# rocketBoard.net
KiCad netlist of a schematic drawn in EAGLE
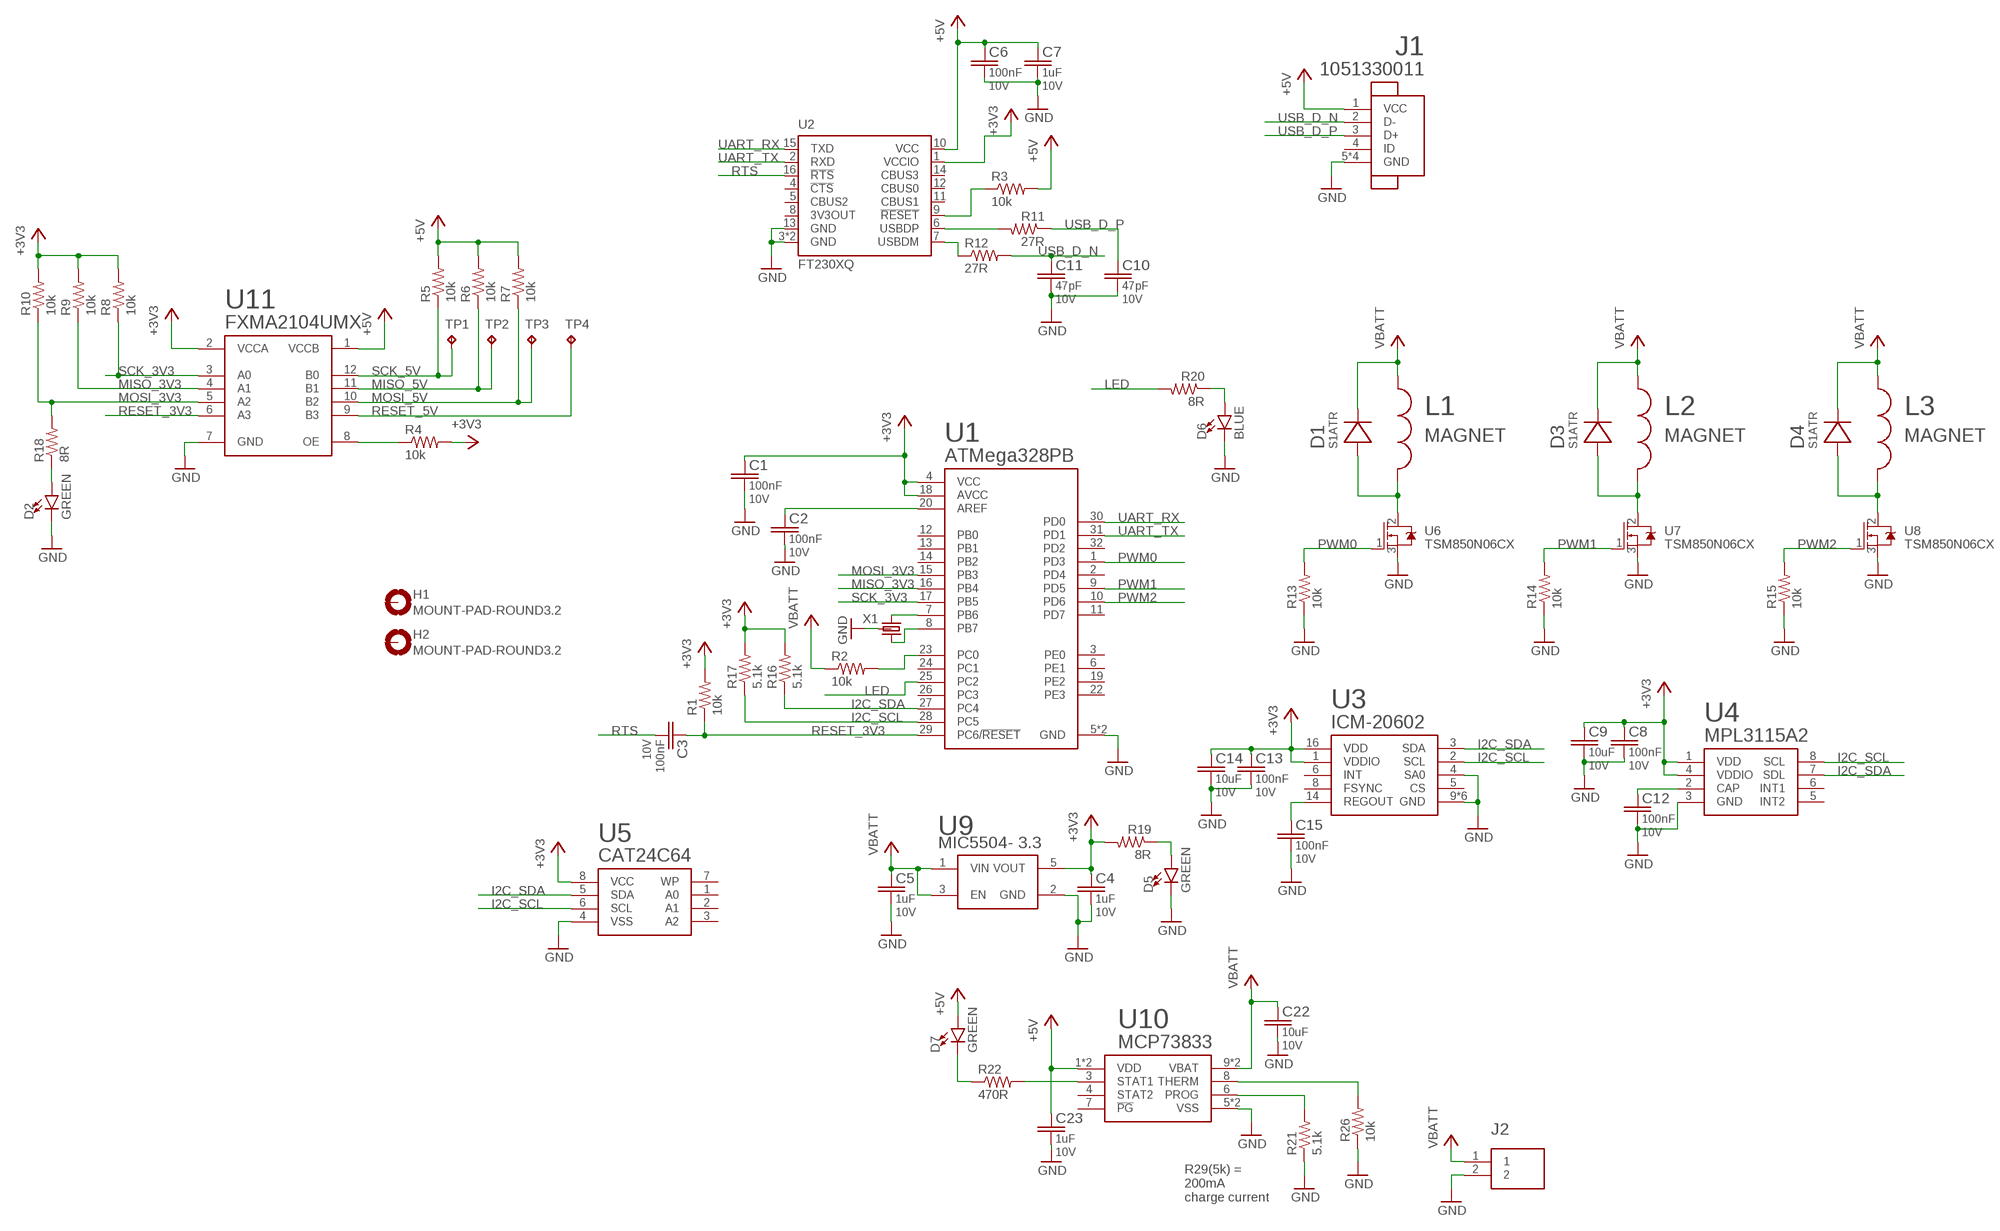
[diagram p0: schematic, sheet 1]

(export (version "E")
  (design (tool "Eeschema 10.0.6"))
  (components
    (comp (ref "C1")
      (value "100nF")
      (footprint "eagle-import:C0402")
      (fields (field (name "RATING") "10V"))
      (libsource (lib "eagle-import") (part "CL05A104MP5NNNC"))
    )
    (comp (ref "C2")
      (value "100nF")
      (footprint "eagle-import:C0402")
      (fields (field (name "RATING") "10V"))
      (libsource (lib "eagle-import") (part "CL05A104MP5NNNC"))
    )
    (comp (ref "C3")
      (value "100nF")
      (footprint "eagle-import:C0402")
      (fields (field (name "RATING") "10V"))
      (libsource (lib "eagle-import") (part "CL05A104MP5NNNC"))
    )
    (comp (ref "C4")
      (value "1uF")
      (footprint "eagle-import:C0402")
      (fields (field (name "RATING") "10V"))
      (libsource (lib "eagle-import") (part "CL05A105MP5NNNC"))
    )
    (comp (ref "C5")
      (value "1uF")
      (footprint "eagle-import:C0402")
      (fields (field (name "RATING") "10V"))
      (libsource (lib "eagle-import") (part "CL05A105MP5NNNC"))
    )
    (comp (ref "C6")
      (value "100nF")
      (footprint "eagle-import:C0402")
      (fields (field (name "RATING") "10V"))
      (libsource (lib "eagle-import") (part "CL05A104MP5NNNC"))
    )
    (comp (ref "C7")
      (value "1uF")
      (footprint "eagle-import:C0402")
      (fields (field (name "RATING") "10V"))
      (libsource (lib "eagle-import") (part "CL05A105MP5NNNC"))
    )
    (comp (ref "C8")
      (value "100nF")
      (footprint "eagle-import:C0402")
      (fields (field (name "RATING") "10V"))
      (libsource (lib "eagle-import") (part "CL05A104MP5NNNC"))
    )
    (comp (ref "C9")
      (value "10uF")
      (footprint "eagle-import:C0603")
      (fields (field (name "RATING") "10V"))
      (libsource (lib "eagle-import") (part "GRM188R61A106KE69D"))
    )
    (comp (ref "C10")
      (value "47pF")
      (footprint "eagle-import:C0402")
      (fields (field (name "RATING") "10V"))
      (libsource (lib "eagle-import") (part "885012005011"))
    )
    (comp (ref "C11")
      (value "47pF")
      (footprint "eagle-import:C0402")
      (fields (field (name "RATING") "10V"))
      (libsource (lib "eagle-import") (part "885012005011"))
    )
    (comp (ref "C12")
      (value "100nF")
      (footprint "eagle-import:C0402")
      (fields (field (name "RATING") "10V"))
      (libsource (lib "eagle-import") (part "CL05A104MP5NNNC"))
    )
    (comp (ref "C13")
      (value "100nF")
      (footprint "eagle-import:C0402")
      (fields (field (name "RATING") "10V"))
      (libsource (lib "eagle-import") (part "CL05A104MP5NNNC"))
    )
    (comp (ref "C14")
      (value "10uF")
      (footprint "eagle-import:C0603")
      (fields (field (name "RATING") "10V"))
      (libsource (lib "eagle-import") (part "GRM188R61A106KE69D"))
    )
    (comp (ref "C15")
      (value "100nF")
      (footprint "eagle-import:C0402")
      (fields (field (name "RATING") "10V"))
      (libsource (lib "eagle-import") (part "CL05A104MP5NNNC"))
    )
    (comp (ref "C22")
      (value "10uF")
      (footprint "eagle-import:C0603")
      (fields (field (name "RATING") "10V"))
      (libsource (lib "eagle-import") (part "GRM188R61A106KE69D"))
    )
    (comp (ref "C23")
      (value "1uF")
      (footprint "eagle-import:C0402")
      (fields (field (name "RATING") "10V"))
      (libsource (lib "eagle-import") (part "CL05A105MP5NNNC"))
    )
    (comp (ref "D1")
      (value "S1ATRSMA")
      (footprint "eagle-import:SODFL5226X295")
      (libsource (lib "eagle-import") (part "S1ATRSMA"))
    )
    (comp (ref "D2")
      (value "GREEN")
      (footprint "eagle-import:LED-0603")
      (libsource (lib "eagle-import") (part "LED-GREEN0603"))
    )
    (comp (ref "D3")
      (value "S1ATRSMA")
      (footprint "eagle-import:SODFL5226X295")
      (libsource (lib "eagle-import") (part "S1ATRSMA"))
    )
    (comp (ref "D4")
      (value "S1ATRSMA")
      (footprint "eagle-import:SODFL5226X295")
      (libsource (lib "eagle-import") (part "S1ATRSMA"))
    )
    (comp (ref "D5")
      (value "GREEN")
      (footprint "eagle-import:LED-0603")
      (libsource (lib "eagle-import") (part "LED-GREEN0603"))
    )
    (comp (ref "D6")
      (value "BLUE")
      (footprint "eagle-import:LED-0603")
      (libsource (lib "eagle-import") (part "LED-GREEN0603"))
    )
    (comp (ref "D7")
      (value "GREEN")
      (footprint "eagle-import:LED-0603")
      (libsource (lib "eagle-import") (part "LED-GREEN0603"))
    )
    (comp (ref "H1")
      (value "MOUNT-PAD-ROUND3.2")
      (footprint "eagle-import:3,2-PAD")
      (libsource (lib "eagle-import") (part "MOUNT-PAD-ROUND3.2"))
    )
    (comp (ref "H2")
      (value "MOUNT-PAD-ROUND3.2")
      (footprint "eagle-import:3,2-PAD")
      (libsource (lib "eagle-import") (part "MOUNT-PAD-ROUND3.2"))
    )
    (comp (ref "J1")
      (value "1051330011")
      (footprint "eagle-import:1051330011")
      (libsource (lib "eagle-import") (part "1051330011"))
    )
    (comp (ref "J2")
      (value "2_PIN_CONNECTOR")
      (footprint "eagle-import:XH_CONNECTOR")
      (libsource (lib "eagle-import") (part "2_PIN_CONNECTOR"))
    )
    (comp (ref "L1")
      (value "MAGNET")
      (footprint "eagle-import:MAGNET")
      (libsource (lib "eagle-import") (part "MAGNET"))
    )
    (comp (ref "L2")
      (value "MAGNET")
      (footprint "eagle-import:MAGNET")
      (libsource (lib "eagle-import") (part "MAGNET"))
    )
    (comp (ref "L3")
      (value "MAGNET")
      (footprint "eagle-import:MAGNET")
      (libsource (lib "eagle-import") (part "MAGNET"))
    )
    (comp (ref "R1")
      (value "10k")
      (footprint "eagle-import:R0402")
      (libsource (lib "eagle-import") (part "RC0402JR-0710KL"))
    )
    (comp (ref "R2")
      (value "10k")
      (footprint "eagle-import:R0402")
      (libsource (lib "eagle-import") (part "RC0402JR-0710KL"))
    )
    (comp (ref "R3")
      (value "10k")
      (footprint "eagle-import:R0402")
      (libsource (lib "eagle-import") (part "RC0402JR-0710KL"))
    )
    (comp (ref "R4")
      (value "10k")
      (footprint "eagle-import:R0402")
      (libsource (lib "eagle-import") (part "RC0402JR-0710KL"))
    )
    (comp (ref "R5")
      (value "10k")
      (footprint "eagle-import:R0402")
      (libsource (lib "eagle-import") (part "RC0402JR-0710KL"))
    )
    (comp (ref "R6")
      (value "10k")
      (footprint "eagle-import:R0402")
      (libsource (lib "eagle-import") (part "RC0402JR-0710KL"))
    )
    (comp (ref "R7")
      (value "10k")
      (footprint "eagle-import:R0402")
      (libsource (lib "eagle-import") (part "RC0402JR-0710KL"))
    )
    (comp (ref "R8")
      (value "10k")
      (footprint "eagle-import:R0402")
      (libsource (lib "eagle-import") (part "RC0402JR-0710KL"))
    )
    (comp (ref "R9")
      (value "10k")
      (footprint "eagle-import:R0402")
      (libsource (lib "eagle-import") (part "RC0402JR-0710KL"))
    )
    (comp (ref "R10")
      (value "10k")
      (footprint "eagle-import:R0402")
      (libsource (lib "eagle-import") (part "RC0402JR-0710KL"))
    )
    (comp (ref "R11")
      (value "27R")
      (footprint "eagle-import:R0402")
      (libsource (lib "eagle-import") (part "RMCF0402JT27R0"))
    )
    (comp (ref "R12")
      (value "27R")
      (footprint "eagle-import:R0402")
      (libsource (lib "eagle-import") (part "RMCF0402JT27R0"))
    )
    (comp (ref "R13")
      (value "10k")
      (footprint "eagle-import:R0402")
      (libsource (lib "eagle-import") (part "RC0402JR-0710KL"))
    )
    (comp (ref "R14")
      (value "10k")
      (footprint "eagle-import:R0402")
      (libsource (lib "eagle-import") (part "RC0402JR-0710KL"))
    )
    (comp (ref "R15")
      (value "10k")
      (footprint "eagle-import:R0402")
      (libsource (lib "eagle-import") (part "RC0402JR-0710KL"))
    )
    (comp (ref "R16")
      (value "5.1k")
      (footprint "eagle-import:R0402")
      (libsource (lib "eagle-import") (part "RC0402JR-075K1L"))
    )
    (comp (ref "R17")
      (value "5.1k")
      (footprint "eagle-import:R0402")
      (libsource (lib "eagle-import") (part "RC0402JR-075K1L"))
    )
    (comp (ref "R18")
      (value "8R")
      (footprint "eagle-import:R0402")
      (libsource (lib "eagle-import") (part "RMCF0402JT8R20"))
    )
    (comp (ref "R19")
      (value "8R")
      (footprint "eagle-import:R0402")
      (libsource (lib "eagle-import") (part "RMCF0402JT8R20"))
    )
    (comp (ref "R20")
      (value "8R")
      (footprint "eagle-import:R0402")
      (libsource (lib "eagle-import") (part "RMCF0402JT8R20"))
    )
    (comp (ref "R21")
      (value "5.1k")
      (footprint "eagle-import:R0402")
      (libsource (lib "eagle-import") (part "RC0402JR-075K1L"))
    )
    (comp (ref "R22")
      (value "470R")
      (footprint "eagle-import:R0402")
      (libsource (lib "eagle-import") (part "RC0402JR-07470RL"))
    )
    (comp (ref "R26")
      (value "10k")
      (footprint "eagle-import:R0402")
      (libsource (lib "eagle-import") (part "RC0402JR-0710KL"))
    )
    (comp (ref "TP1")
      (value "TPTP20R")
      (footprint "eagle-import:TP20R")
      (libsource (lib "eagle-import") (part "TPTP20R"))
    )
    (comp (ref "TP2")
      (value "TPTP20R")
      (footprint "eagle-import:TP20R")
      (libsource (lib "eagle-import") (part "TPTP20R"))
    )
    (comp (ref "TP3")
      (value "TPTP20R")
      (footprint "eagle-import:TP20R")
      (libsource (lib "eagle-import") (part "TPTP20R"))
    )
    (comp (ref "TP4")
      (value "TPTP20R")
      (footprint "eagle-import:TP20R")
      (libsource (lib "eagle-import") (part "TPTP20R"))
    )
    (comp (ref "U1")
      (value "ATMEGA328PBVQFN")
      (footprint "eagle-import:QFN50P500X500X90-32")
      (libsource (lib "eagle-import") (part "ATMEGA328PBVQFN"))
    )
    (comp (ref "U2")
      (value "FT230XQ")
      (footprint "eagle-import:QFN16")
      (libsource (lib "eagle-import") (part "FT230XQ"))
    )
    (comp (ref "U3")
      (value "ICM-20602")
      (footprint "eagle-import:LGA16")
      (libsource (lib "eagle-import") (part "ICM-20602"))
    )
    (comp (ref "U4")
      (value "MPL3115A2")
      (footprint "eagle-import:LGA8")
      (libsource (lib "eagle-import") (part "MPL3115A2"))
    )
    (comp (ref "U5")
      (value "CAT24C64SOIC8")
      (footprint "eagle-import:SOIC127P600X175-8")
      (libsource (lib "eagle-import") (part "CAT24C64SOIC8"))
    )
    (comp (ref "U6")
      (value "TSM850N06CX")
      (footprint "eagle-import:SOT95P280X110-3")
      (libsource (lib "eagle-import") (part "TSM850N06CXSOT23"))
    )
    (comp (ref "U7")
      (value "TSM850N06CX")
      (footprint "eagle-import:SOT95P280X110-3")
      (libsource (lib "eagle-import") (part "TSM850N06CXSOT23"))
    )
    (comp (ref "U8")
      (value "TSM850N06CX")
      (footprint "eagle-import:SOT95P280X110-3")
      (libsource (lib "eagle-import") (part "TSM850N06CXSOT23"))
    )
    (comp (ref "U9")
      (value "3.3")
      (footprint "eagle-import:SOT23-5")
      (libsource (lib "eagle-import") (part "MIC5504-3.3"))
    )
    (comp (ref "U10")
      (value "MCP73833")
      (footprint "eagle-import:DFN10-3X3")
      (libsource (lib "eagle-import") (part "MCP73833"))
    )
    (comp (ref "U11")
      (value "FXMA2104UMX")
      (footprint "eagle-import:12MLP")
      (libsource (lib "eagle-import") (part "FXMA2104UMX"))
    )
    (comp (ref "X1")
      (value "CSTCE8M00G55")
      (footprint "eagle-import:3-SMD")
      (libsource (lib "eagle-import") (part "CSTCE8M00G55"))
    )
  )
  (nets
    (net (code "1") (name "+3V3") (class "Default")
      (node (ref "C1") (pin "1") (pinfunction "1_1") (pintype "bidirectional"))
      (node (ref "C13") (pin "1") (pinfunction "1_1") (pintype "bidirectional"))
      (node (ref "C14") (pin "1") (pinfunction "1_1") (pintype "bidirectional"))
      (node (ref "C4") (pin "1") (pinfunction "1_1") (pintype "bidirectional"))
      (node (ref "C8") (pin "1") (pinfunction "1_1") (pintype "bidirectional"))
      (node (ref "C9") (pin "1") (pinfunction "1_1") (pintype "bidirectional"))
      (node (ref "R1") (pin "2") (pinfunction "2_2") (pintype "passive"))
      (node (ref "R10") (pin "2") (pinfunction "2_2") (pintype "passive"))
      (node (ref "R16") (pin "2") (pinfunction "2_2") (pintype "passive"))
      (node (ref "R17") (pin "2") (pinfunction "2_2") (pintype "passive"))
      (node (ref "R19") (pin "2") (pinfunction "2_2") (pintype "passive"))
      (node (ref "R4") (pin "2") (pinfunction "2_2") (pintype "passive"))
      (node (ref "R8") (pin "2") (pinfunction "2_2") (pintype "passive"))
      (node (ref "R9") (pin "2") (pinfunction "2_2") (pintype "passive"))
      (node (ref "U1") (pin "18") (pinfunction "AVCC_18") (pintype "bidirectional"))
      (node (ref "U1") (pin "4") (pinfunction "VCC_4") (pintype "bidirectional"))
      (node (ref "U11") (pin "2") (pinfunction "VCCA_2") (pintype "bidirectional"))
      (node (ref "U2") (pin "1") (pinfunction "VCCIO_1") (pintype "power_in"))
      (node (ref "U3") (pin "1") (pinfunction "VDDIO_1") (pintype "bidirectional"))
      (node (ref "U3") (pin "16") (pinfunction "VDD_16") (pintype "bidirectional"))
      (node (ref "U4") (pin "1") (pinfunction "VDD_1") (pintype "bidirectional"))
      (node (ref "U4") (pin "4") (pinfunction "VDDIO_4") (pintype "bidirectional"))
      (node (ref "U5") (pin "8") (pinfunction "VCC_8") (pintype "bidirectional"))
      (node (ref "U9") (pin "5") (pinfunction "VOUT_5") (pintype "bidirectional"))
    )
    (net (code "2") (name "+5V") (class "Default")
      (node (ref "C23") (pin "1") (pinfunction "1_1") (pintype "bidirectional"))
      (node (ref "C6") (pin "1") (pinfunction "1_1") (pintype "bidirectional"))
      (node (ref "C7") (pin "1") (pinfunction "1_1") (pintype "bidirectional"))
      (node (ref "D7") (pin "A") (pinfunction "A_A") (pintype "passive"))
      (node (ref "J1") (pin "1") (pinfunction "VCC_1") (pintype "bidirectional"))
      (node (ref "R3") (pin "2") (pinfunction "2_2") (pintype "passive"))
      (node (ref "R5") (pin "2") (pinfunction "2_2") (pintype "passive"))
      (node (ref "R6") (pin "2") (pinfunction "2_2") (pintype "passive"))
      (node (ref "R7") (pin "2") (pinfunction "2_2") (pintype "passive"))
      (node (ref "U10") (pin "1") (pinfunction "VDD_1") (pintype "bidirectional"))
      (node (ref "U10") (pin "2") (pinfunction "VDD_2") (pintype "bidirectional"))
      (node (ref "U11") (pin "1") (pinfunction "VCCB_1") (pintype "bidirectional"))
      (node (ref "U2") (pin "10") (pinfunction "VCC_10") (pintype "power_in"))
    )
    (net (code "3") (name "/I2C_SCL") (class "Default")
      (node (ref "R17") (pin "1") (pinfunction "1_1") (pintype "passive"))
      (node (ref "U1") (pin "28") (pinfunction "PC5_28") (pintype "bidirectional"))
      (node (ref "U3") (pin "2") (pinfunction "SCL_2") (pintype "bidirectional"))
      (node (ref "U4") (pin "8") (pinfunction "SCL_8") (pintype "bidirectional"))
      (node (ref "U5") (pin "6") (pinfunction "SCL_6") (pintype "bidirectional"))
    )
    (net (code "4") (name "/I2C_SDA") (class "Default")
      (node (ref "R16") (pin "1") (pinfunction "1_1") (pintype "passive"))
      (node (ref "U1") (pin "27") (pinfunction "PC4_27") (pintype "bidirectional"))
      (node (ref "U3") (pin "3") (pinfunction "SDA_3") (pintype "bidirectional"))
      (node (ref "U4") (pin "7") (pinfunction "SDL_7") (pintype "bidirectional"))
      (node (ref "U5") (pin "5") (pinfunction "SDA_5") (pintype "bidirectional"))
    )
    (net (code "5") (name "/LED") (class "Default")
      (node (ref "R20") (pin "2") (pinfunction "2_2") (pintype "passive"))
      (node (ref "U1") (pin "25") (pinfunction "PC2_25") (pintype "bidirectional"))
    )
    (net (code "6") (name "/MISO_3V3") (class "Default")
      (node (ref "R9") (pin "1") (pinfunction "1_1") (pintype "passive"))
      (node (ref "U1") (pin "16") (pinfunction "PB4_16") (pintype "bidirectional"))
      (node (ref "U11") (pin "4") (pinfunction "A1_4") (pintype "bidirectional"))
    )
    (net (code "7") (name "/MISO_5V") (class "Default")
      (node (ref "R6") (pin "1") (pinfunction "1_1") (pintype "passive"))
      (node (ref "TP2") (pin "TP") (pinfunction "TP_TP") (pintype "input"))
      (node (ref "U11") (pin "11") (pinfunction "B1_11") (pintype "bidirectional"))
    )
    (net (code "8") (name "/MOSI_3V3") (class "Default")
      (node (ref "R10") (pin "1") (pinfunction "1_1") (pintype "passive"))
      (node (ref "R18") (pin "2") (pinfunction "2_2") (pintype "passive"))
      (node (ref "U1") (pin "15") (pinfunction "PB3_15") (pintype "bidirectional"))
      (node (ref "U11") (pin "5") (pinfunction "A2_5") (pintype "bidirectional"))
    )
    (net (code "9") (name "/MOSI_5V") (class "Default")
      (node (ref "R7") (pin "1") (pinfunction "1_1") (pintype "passive"))
      (node (ref "TP3") (pin "TP") (pinfunction "TP_TP") (pintype "input"))
      (node (ref "U11") (pin "10") (pinfunction "B2_10") (pintype "bidirectional"))
    )
    (net (code "10") (name "/PWM0") (class "Default")
      (node (ref "R13") (pin "2") (pinfunction "2_2") (pintype "passive"))
      (node (ref "U1") (pin "1") (pinfunction "PD3_1") (pintype "bidirectional"))
      (node (ref "U6") (pin "1") (pinfunction "G_1") (pintype "passive"))
    )
    (net (code "11") (name "/PWM1") (class "Default")
      (node (ref "R14") (pin "2") (pinfunction "2_2") (pintype "passive"))
      (node (ref "U1") (pin "9") (pinfunction "PD5_9") (pintype "bidirectional"))
      (node (ref "U7") (pin "1") (pinfunction "G_1") (pintype "passive"))
    )
    (net (code "12") (name "/PWM2") (class "Default")
      (node (ref "R15") (pin "2") (pinfunction "2_2") (pintype "passive"))
      (node (ref "U1") (pin "10") (pinfunction "PD6_10") (pintype "bidirectional"))
      (node (ref "U8") (pin "1") (pinfunction "G_1") (pintype "passive"))
    )
    (net (code "13") (name "/RESET_3V3") (class "Default")
      (node (ref "C3") (pin "1") (pinfunction "1_1") (pintype "bidirectional"))
      (node (ref "R1") (pin "1") (pinfunction "1_1") (pintype "passive"))
      (node (ref "U1") (pin "29") (pinfunction "PC6/~{RESET}_29") (pintype "bidirectional"))
      (node (ref "U11") (pin "6") (pinfunction "A3_6") (pintype "bidirectional"))
    )
    (net (code "14") (name "/RESET_5V") (class "Default")
      (node (ref "TP4") (pin "TP") (pinfunction "TP_TP") (pintype "input"))
      (node (ref "U11") (pin "9") (pinfunction "B3_9") (pintype "bidirectional"))
    )
    (net (code "15") (name "/RTS") (class "Default")
      (node (ref "C3") (pin "2") (pinfunction "2_2") (pintype "bidirectional"))
      (node (ref "U2") (pin "16") (pinfunction "~{RTS}_16") (pintype "output"))
    )
    (net (code "16") (name "/SCK_3V3") (class "Default")
      (node (ref "R8") (pin "1") (pinfunction "1_1") (pintype "passive"))
      (node (ref "U1") (pin "17") (pinfunction "PB5_17") (pintype "bidirectional"))
      (node (ref "U11") (pin "3") (pinfunction "A0_3") (pintype "bidirectional"))
    )
    (net (code "17") (name "/SCK_5V") (class "Default")
      (node (ref "R5") (pin "1") (pinfunction "1_1") (pintype "passive"))
      (node (ref "TP1") (pin "TP") (pinfunction "TP_TP") (pintype "input"))
      (node (ref "U11") (pin "12") (pinfunction "B0_12") (pintype "bidirectional"))
    )
    (net (code "18") (name "/UART_RX") (class "Default")
      (node (ref "U1") (pin "30") (pinfunction "PD0_30") (pintype "bidirectional"))
      (node (ref "U2") (pin "15") (pinfunction "TXD_15") (pintype "output"))
    )
    (net (code "19") (name "/UART_TX") (class "Default")
      (node (ref "U1") (pin "31") (pinfunction "PD1_31") (pintype "bidirectional"))
      (node (ref "U2") (pin "2") (pinfunction "RXD_2") (pintype "input"))
    )
    (net (code "20") (name "/USB_D_N") (class "Default")
      (node (ref "C11") (pin "1") (pinfunction "1_1") (pintype "bidirectional"))
      (node (ref "J1") (pin "2") (pinfunction "D-_2") (pintype "bidirectional"))
      (node (ref "R12") (pin "2") (pinfunction "2_2") (pintype "passive"))
    )
    (net (code "21") (name "/USB_D_P") (class "Default")
      (node (ref "C10") (pin "1") (pinfunction "1_1") (pintype "bidirectional"))
      (node (ref "J1") (pin "3") (pinfunction "D+_3") (pintype "bidirectional"))
      (node (ref "R11") (pin "1") (pinfunction "1_1") (pintype "passive"))
    )
    (net (code "22") (name "GND") (class "Default")
      (node (ref "C1") (pin "2") (pinfunction "2_2") (pintype "bidirectional"))
      (node (ref "C10") (pin "2") (pinfunction "2_2") (pintype "bidirectional"))
      (node (ref "C11") (pin "2") (pinfunction "2_2") (pintype "bidirectional"))
      (node (ref "C12") (pin "2") (pinfunction "2_2") (pintype "bidirectional"))
      (node (ref "C13") (pin "2") (pinfunction "2_2") (pintype "bidirectional"))
      (node (ref "C14") (pin "2") (pinfunction "2_2") (pintype "bidirectional"))
      (node (ref "C15") (pin "2") (pinfunction "2_2") (pintype "bidirectional"))
      (node (ref "C2") (pin "2") (pinfunction "2_2") (pintype "bidirectional"))
      (node (ref "C22") (pin "2") (pinfunction "2_2") (pintype "bidirectional"))
      (node (ref "C23") (pin "2") (pinfunction "2_2") (pintype "bidirectional"))
      (node (ref "C4") (pin "2") (pinfunction "2_2") (pintype "bidirectional"))
      (node (ref "C5") (pin "2") (pinfunction "2_2") (pintype "bidirectional"))
      (node (ref "C6") (pin "2") (pinfunction "2_2") (pintype "bidirectional"))
      (node (ref "C7") (pin "2") (pinfunction "2_2") (pintype "bidirectional"))
      (node (ref "C8") (pin "2") (pinfunction "2_2") (pintype "bidirectional"))
      (node (ref "C9") (pin "2") (pinfunction "2_2") (pintype "bidirectional"))
      (node (ref "D2") (pin "C") (pinfunction "C_C") (pintype "passive"))
      (node (ref "D5") (pin "C") (pinfunction "C_C") (pintype "passive"))
      (node (ref "D6") (pin "C") (pinfunction "C_C") (pintype "passive"))
      (node (ref "J1") (pin "5") (pinfunction "GND_5") (pintype "bidirectional"))
      (node (ref "J1") (pin "P$1") (pinfunction "GND_P$1") (pintype "bidirectional"))
      (node (ref "J1") (pin "P$2") (pinfunction "GND_P$2") (pintype "bidirectional"))
      (node (ref "J1") (pin "P$3") (pinfunction "GND_P$3") (pintype "bidirectional"))
      (node (ref "J2") (pin "2") (pinfunction "2_2") (pintype "bidirectional"))
      (node (ref "R13") (pin "1") (pinfunction "1_1") (pintype "passive"))
      (node (ref "R14") (pin "1") (pinfunction "1_1") (pintype "passive"))
      (node (ref "R15") (pin "1") (pinfunction "1_1") (pintype "passive"))
      (node (ref "R21") (pin "1") (pinfunction "1_1") (pintype "passive"))
      (node (ref "R26") (pin "1") (pinfunction "1_1") (pintype "passive"))
      (node (ref "U1") (pin "21") (pinfunction "GND_21") (pintype "bidirectional"))
      (node (ref "U1") (pin "5") (pinfunction "GND_5") (pintype "bidirectional"))
      (node (ref "U10") (pin "5") (pinfunction "VSS_5") (pintype "bidirectional"))
      (node (ref "U10") (pin "EXP") (pinfunction "VSS_EXP") (pintype "bidirectional"))
      (node (ref "U11") (pin "7") (pinfunction "GND_7") (pintype "bidirectional"))
      (node (ref "U2") (pin "13") (pinfunction "GND_13") (pintype "power_in"))
      (node (ref "U2") (pin "3") (pinfunction "GND_3") (pintype "power_in"))
      (node (ref "U2") (pin "TAB") (pinfunction "GND_TAB") (pintype "power_in"))
      (node (ref "U3") (pin "10") (pinfunction "GND_10") (pintype "bidirectional"))
      (node (ref "U3") (pin "11") (pinfunction "GND_11") (pintype "bidirectional"))
      (node (ref "U3") (pin "12") (pinfunction "GND_12") (pintype "bidirectional"))
      (node (ref "U3") (pin "13") (pinfunction "GND_13") (pintype "bidirectional"))
      (node (ref "U3") (pin "15") (pinfunction "GND_15") (pintype "bidirectional"))
      (node (ref "U3") (pin "4") (pinfunction "SA0_4") (pintype "bidirectional"))
      (node (ref "U3") (pin "9") (pinfunction "GND_9") (pintype "bidirectional"))
      (node (ref "U4") (pin "3") (pinfunction "GND_3") (pintype "bidirectional"))
      (node (ref "U5") (pin "4") (pinfunction "VSS_4") (pintype "bidirectional"))
      (node (ref "U6") (pin "3") (pinfunction "S_3") (pintype "passive"))
      (node (ref "U7") (pin "3") (pinfunction "S_3") (pintype "passive"))
      (node (ref "U8") (pin "3") (pinfunction "S_3") (pintype "passive"))
      (node (ref "U9") (pin "2") (pinfunction "GND_2") (pintype "bidirectional"))
      (node (ref "X1") (pin "2") (pinfunction "GND_2") (pintype "bidirectional"))
    )
    (net (code "23") (name "Net-(D2-PadA)") (class "Default")
      (node (ref "D2") (pin "A") (pinfunction "A_A") (pintype "passive"))
      (node (ref "R18") (pin "1") (pinfunction "1_1") (pintype "passive"))
    )
    (net (code "24") (name "Net-(D5-PadA)") (class "Default")
      (node (ref "D5") (pin "A") (pinfunction "A_A") (pintype "passive"))
      (node (ref "R19") (pin "1") (pinfunction "1_1") (pintype "passive"))
    )
    (net (code "25") (name "Net-(D6-PadA)") (class "Default")
      (node (ref "D6") (pin "A") (pinfunction "A_A") (pintype "passive"))
      (node (ref "R20") (pin "1") (pinfunction "1_1") (pintype "passive"))
    )
    (net (code "26") (name "Net-(D7-PadC)") (class "Default")
      (node (ref "D7") (pin "C") (pinfunction "C_C") (pintype "passive"))
      (node (ref "R22") (pin "1") (pinfunction "1_1") (pintype "passive"))
    )
    (net (code "27") (name "Net-(U1-AREF)") (class "Default")
      (node (ref "C2") (pin "1") (pinfunction "1_1") (pintype "bidirectional"))
      (node (ref "U1") (pin "20") (pinfunction "AREF_20") (pintype "bidirectional"))
    )
    (net (code "28") (name "Net-(U1-PB6)") (class "Default")
      (node (ref "U1") (pin "7") (pinfunction "PB6_7") (pintype "bidirectional"))
      (node (ref "X1") (pin "1") (pinfunction "1_1") (pintype "passive"))
    )
    (net (code "29") (name "Net-(U1-PB7)") (class "Default")
      (node (ref "U1") (pin "8") (pinfunction "PB7_8") (pintype "bidirectional"))
      (node (ref "X1") (pin "3") (pinfunction "2_3") (pintype "passive"))
    )
    (net (code "30") (name "Net-(U1-PC0)") (class "Default")
      (node (ref "R2") (pin "2") (pinfunction "2_2") (pintype "passive"))
      (node (ref "U1") (pin "23") (pinfunction "PC0_23") (pintype "bidirectional"))
    )
    (net (code "31") (name "Net-(U2-USBDM)") (class "Default")
      (node (ref "R12") (pin "1") (pinfunction "1_1") (pintype "passive"))
      (node (ref "U2") (pin "7") (pinfunction "USBDM_7") (pintype "input"))
    )
    (net (code "32") (name "Net-(U2-USBDP)") (class "Default")
      (node (ref "R11") (pin "2") (pinfunction "2_2") (pintype "passive"))
      (node (ref "U2") (pin "6") (pinfunction "USBDP_6") (pintype "input"))
    )
    (net (code "33") (name "Net-(U2-~{RESET})") (class "Default")
      (node (ref "R3") (pin "1") (pinfunction "1_1") (pintype "passive"))
      (node (ref "U2") (pin "9") (pinfunction "~{RESET}_9") (pintype "input"))
    )
    (net (code "34") (name "Net-(U3-REGOUT)") (class "Default")
      (node (ref "C15") (pin "1") (pinfunction "1_1") (pintype "bidirectional"))
      (node (ref "U3") (pin "14") (pinfunction "REGOUT_14") (pintype "bidirectional"))
    )
    (net (code "35") (name "Net-(U4-CAP)") (class "Default")
      (node (ref "C12") (pin "1") (pinfunction "1_1") (pintype "bidirectional"))
      (node (ref "U4") (pin "2") (pinfunction "CAP_2") (pintype "bidirectional"))
    )
    (net (code "36") (name "Net-(U6-D)") (class "Default")
      (node (ref "D1") (pin "A") (pinfunction "A_A") (pintype "bidirectional"))
      (node (ref "L1") (pin "-") (pinfunction "-_-") (pintype "bidirectional"))
      (node (ref "U6") (pin "2") (pinfunction "D_2") (pintype "passive"))
    )
    (net (code "37") (name "Net-(U7-D)") (class "Default")
      (node (ref "D3") (pin "A") (pinfunction "A_A") (pintype "bidirectional"))
      (node (ref "L2") (pin "-") (pinfunction "-_-") (pintype "bidirectional"))
      (node (ref "U7") (pin "2") (pinfunction "D_2") (pintype "passive"))
    )
    (net (code "38") (name "Net-(U8-D)") (class "Default")
      (node (ref "D4") (pin "A") (pinfunction "A_A") (pintype "bidirectional"))
      (node (ref "L3") (pin "-") (pinfunction "-_-") (pintype "bidirectional"))
      (node (ref "U8") (pin "2") (pinfunction "D_2") (pintype "passive"))
    )
    (net (code "39") (name "Net-(U10-PROG)") (class "Default")
      (node (ref "R21") (pin "2") (pinfunction "2_2") (pintype "passive"))
      (node (ref "U10") (pin "6") (pinfunction "PROG_6") (pintype "bidirectional"))
    )
    (net (code "40") (name "Net-(U10-STAT1)") (class "Default")
      (node (ref "R22") (pin "2") (pinfunction "2_2") (pintype "passive"))
      (node (ref "U10") (pin "3") (pinfunction "STAT1_3") (pintype "bidirectional"))
    )
    (net (code "41") (name "Net-(U10-THERM)") (class "Default")
      (node (ref "R26") (pin "2") (pinfunction "2_2") (pintype "passive"))
      (node (ref "U10") (pin "8") (pinfunction "THERM_8") (pintype "bidirectional"))
    )
    (net (code "42") (name "Net-(U11-OE)") (class "Default")
      (node (ref "R4") (pin "1") (pinfunction "1_1") (pintype "passive"))
      (node (ref "U11") (pin "8") (pinfunction "OE_8") (pintype "bidirectional"))
    )
    (net (code "43") (name "VBATT") (class "Default")
      (node (ref "C22") (pin "1") (pinfunction "1_1") (pintype "bidirectional"))
      (node (ref "C5") (pin "1") (pinfunction "1_1") (pintype "bidirectional"))
      (node (ref "D1") (pin "C") (pinfunction "C_C") (pintype "bidirectional"))
      (node (ref "D3") (pin "C") (pinfunction "C_C") (pintype "bidirectional"))
      (node (ref "D4") (pin "C") (pinfunction "C_C") (pintype "bidirectional"))
      (node (ref "J2") (pin "1") (pinfunction "1_1") (pintype "bidirectional"))
      (node (ref "L1") (pin "+") (pinfunction "+_+") (pintype "bidirectional"))
      (node (ref "L2") (pin "+") (pinfunction "+_+") (pintype "bidirectional"))
      (node (ref "L3") (pin "+") (pinfunction "+_+") (pintype "bidirectional"))
      (node (ref "R2") (pin "1") (pinfunction "1_1") (pintype "passive"))
      (node (ref "U10") (pin "10") (pinfunction "VBAT_10") (pintype "bidirectional"))
      (node (ref "U10") (pin "9") (pinfunction "VBAT_9") (pintype "bidirectional"))
      (node (ref "U9") (pin "1") (pinfunction "VIN_1") (pintype "bidirectional"))
      (node (ref "U9") (pin "3") (pinfunction "EN_3") (pintype "bidirectional"))
    )
    (net (code "44") (name "unconnected-(H1-MOUNT-PadB3,2)") (class "Default")
      (node (ref "H1") (pin "B3,2") (pinfunction "MOUNT_B3,2") (pintype "passive"))
    )
    (net (code "45") (name "unconnected-(H2-MOUNT-PadB3,2)") (class "Default")
      (node (ref "H2") (pin "B3,2") (pinfunction "MOUNT_B3,2") (pintype "passive"))
    )
    (net (code "46") (name "unconnected-(J1-ID-Pad4)") (class "Default")
      (node (ref "J1") (pin "4") (pinfunction "ID_4") (pintype "bidirectional"))
    )
    (net (code "47") (name "unconnected-(U1-PB0-Pad12)") (class "Default")
      (node (ref "U1") (pin "12") (pinfunction "PB0_12") (pintype "bidirectional"))
    )
    (net (code "48") (name "unconnected-(U1-PB1-Pad13)") (class "Default")
      (node (ref "U1") (pin "13") (pinfunction "PB1_13") (pintype "bidirectional"))
    )
    (net (code "49") (name "unconnected-(U1-PB2-Pad14)") (class "Default")
      (node (ref "U1") (pin "14") (pinfunction "PB2_14") (pintype "bidirectional"))
    )
    (net (code "50") (name "unconnected-(U1-PC1-Pad24)") (class "Default")
      (node (ref "U1") (pin "24") (pinfunction "PC1_24") (pintype "bidirectional"))
    )
    (net (code "51") (name "unconnected-(U1-PC3-Pad26)") (class "Default")
      (node (ref "U1") (pin "26") (pinfunction "PC3_26") (pintype "bidirectional"))
    )
    (net (code "52") (name "unconnected-(U1-PD2-Pad32)") (class "Default")
      (node (ref "U1") (pin "32") (pinfunction "PD2_32") (pintype "bidirectional"))
    )
    (net (code "53") (name "unconnected-(U1-PD4-Pad2)") (class "Default")
      (node (ref "U1") (pin "2") (pinfunction "PD4_2") (pintype "bidirectional"))
    )
    (net (code "54") (name "unconnected-(U1-PD7-Pad11)") (class "Default")
      (node (ref "U1") (pin "11") (pinfunction "PD7_11") (pintype "bidirectional"))
    )
    (net (code "55") (name "unconnected-(U1-PE0-Pad3)") (class "Default")
      (node (ref "U1") (pin "3") (pinfunction "PE0_3") (pintype "bidirectional"))
    )
    (net (code "56") (name "unconnected-(U1-PE1-Pad6)") (class "Default")
      (node (ref "U1") (pin "6") (pinfunction "PE1_6") (pintype "bidirectional"))
    )
    (net (code "57") (name "unconnected-(U1-PE2-Pad19)") (class "Default")
      (node (ref "U1") (pin "19") (pinfunction "PE2_19") (pintype "bidirectional"))
    )
    (net (code "58") (name "unconnected-(U1-PE3-Pad22)") (class "Default")
      (node (ref "U1") (pin "22") (pinfunction "PE3_22") (pintype "bidirectional"))
    )
    (net (code "59") (name "unconnected-(U2-3V3OUT-Pad8)") (class "Default")
      (node (ref "U2") (pin "8") (pinfunction "3V3OUT_8") (pintype "output"))
    )
    (net (code "60") (name "unconnected-(U2-CBUS0-Pad12)") (class "Default")
      (node (ref "U2") (pin "12") (pinfunction "CBUS0_12") (pintype "bidirectional"))
    )
    (net (code "61") (name "unconnected-(U2-CBUS1-Pad11)") (class "Default")
      (node (ref "U2") (pin "11") (pinfunction "CBUS1_11") (pintype "bidirectional"))
    )
    (net (code "62") (name "unconnected-(U2-CBUS2-Pad5)") (class "Default")
      (node (ref "U2") (pin "5") (pinfunction "CBUS2_5") (pintype "bidirectional"))
    )
    (net (code "63") (name "unconnected-(U2-CBUS3-Pad14)") (class "Default")
      (node (ref "U2") (pin "14") (pinfunction "CBUS3_14") (pintype "bidirectional"))
    )
    (net (code "64") (name "unconnected-(U2-~{CTS}-Pad4)") (class "Default")
      (node (ref "U2") (pin "4") (pinfunction "~{CTS}_4") (pintype "input"))
    )
    (net (code "65") (name "unconnected-(U3-CS-Pad5)") (class "Default")
      (node (ref "U3") (pin "5") (pinfunction "CS_5") (pintype "bidirectional"))
    )
    (net (code "66") (name "unconnected-(U3-FSYNC-Pad8)") (class "Default")
      (node (ref "U3") (pin "8") (pinfunction "FSYNC_8") (pintype "bidirectional"))
    )
    (net (code "67") (name "unconnected-(U3-INT-Pad6)") (class "Default")
      (node (ref "U3") (pin "6") (pinfunction "INT_6") (pintype "bidirectional"))
    )
    (net (code "68") (name "unconnected-(U4-INT1-Pad6)") (class "Default")
      (node (ref "U4") (pin "6") (pinfunction "INT1_6") (pintype "bidirectional"))
    )
    (net (code "69") (name "unconnected-(U4-INT2-Pad5)") (class "Default")
      (node (ref "U4") (pin "5") (pinfunction "INT2_5") (pintype "bidirectional"))
    )
    (net (code "70") (name "unconnected-(U5-A0-Pad1)") (class "Default")
      (node (ref "U5") (pin "1") (pinfunction "A0_1") (pintype "bidirectional"))
    )
    (net (code "71") (name "unconnected-(U5-A1-Pad2)") (class "Default")
      (node (ref "U5") (pin "2") (pinfunction "A1_2") (pintype "bidirectional"))
    )
    (net (code "72") (name "unconnected-(U5-A2-Pad3)") (class "Default")
      (node (ref "U5") (pin "3") (pinfunction "A2_3") (pintype "bidirectional"))
    )
    (net (code "73") (name "unconnected-(U5-WP-Pad7)") (class "Default")
      (node (ref "U5") (pin "7") (pinfunction "WP_7") (pintype "bidirectional"))
    )
    (net (code "74") (name "unconnected-(U10-STAT2-Pad4)") (class "Default")
      (node (ref "U10") (pin "4") (pinfunction "STAT2_4") (pintype "bidirectional"))
    )
    (net (code "75") (name "unconnected-(U10-~{PG}-Pad7)") (class "Default")
      (node (ref "U10") (pin "7") (pinfunction "~{PG}_7") (pintype "bidirectional"))
    )
  )
)
